# Logic_Board.net
KiCad netlist of a schematic drawn in EAGLE
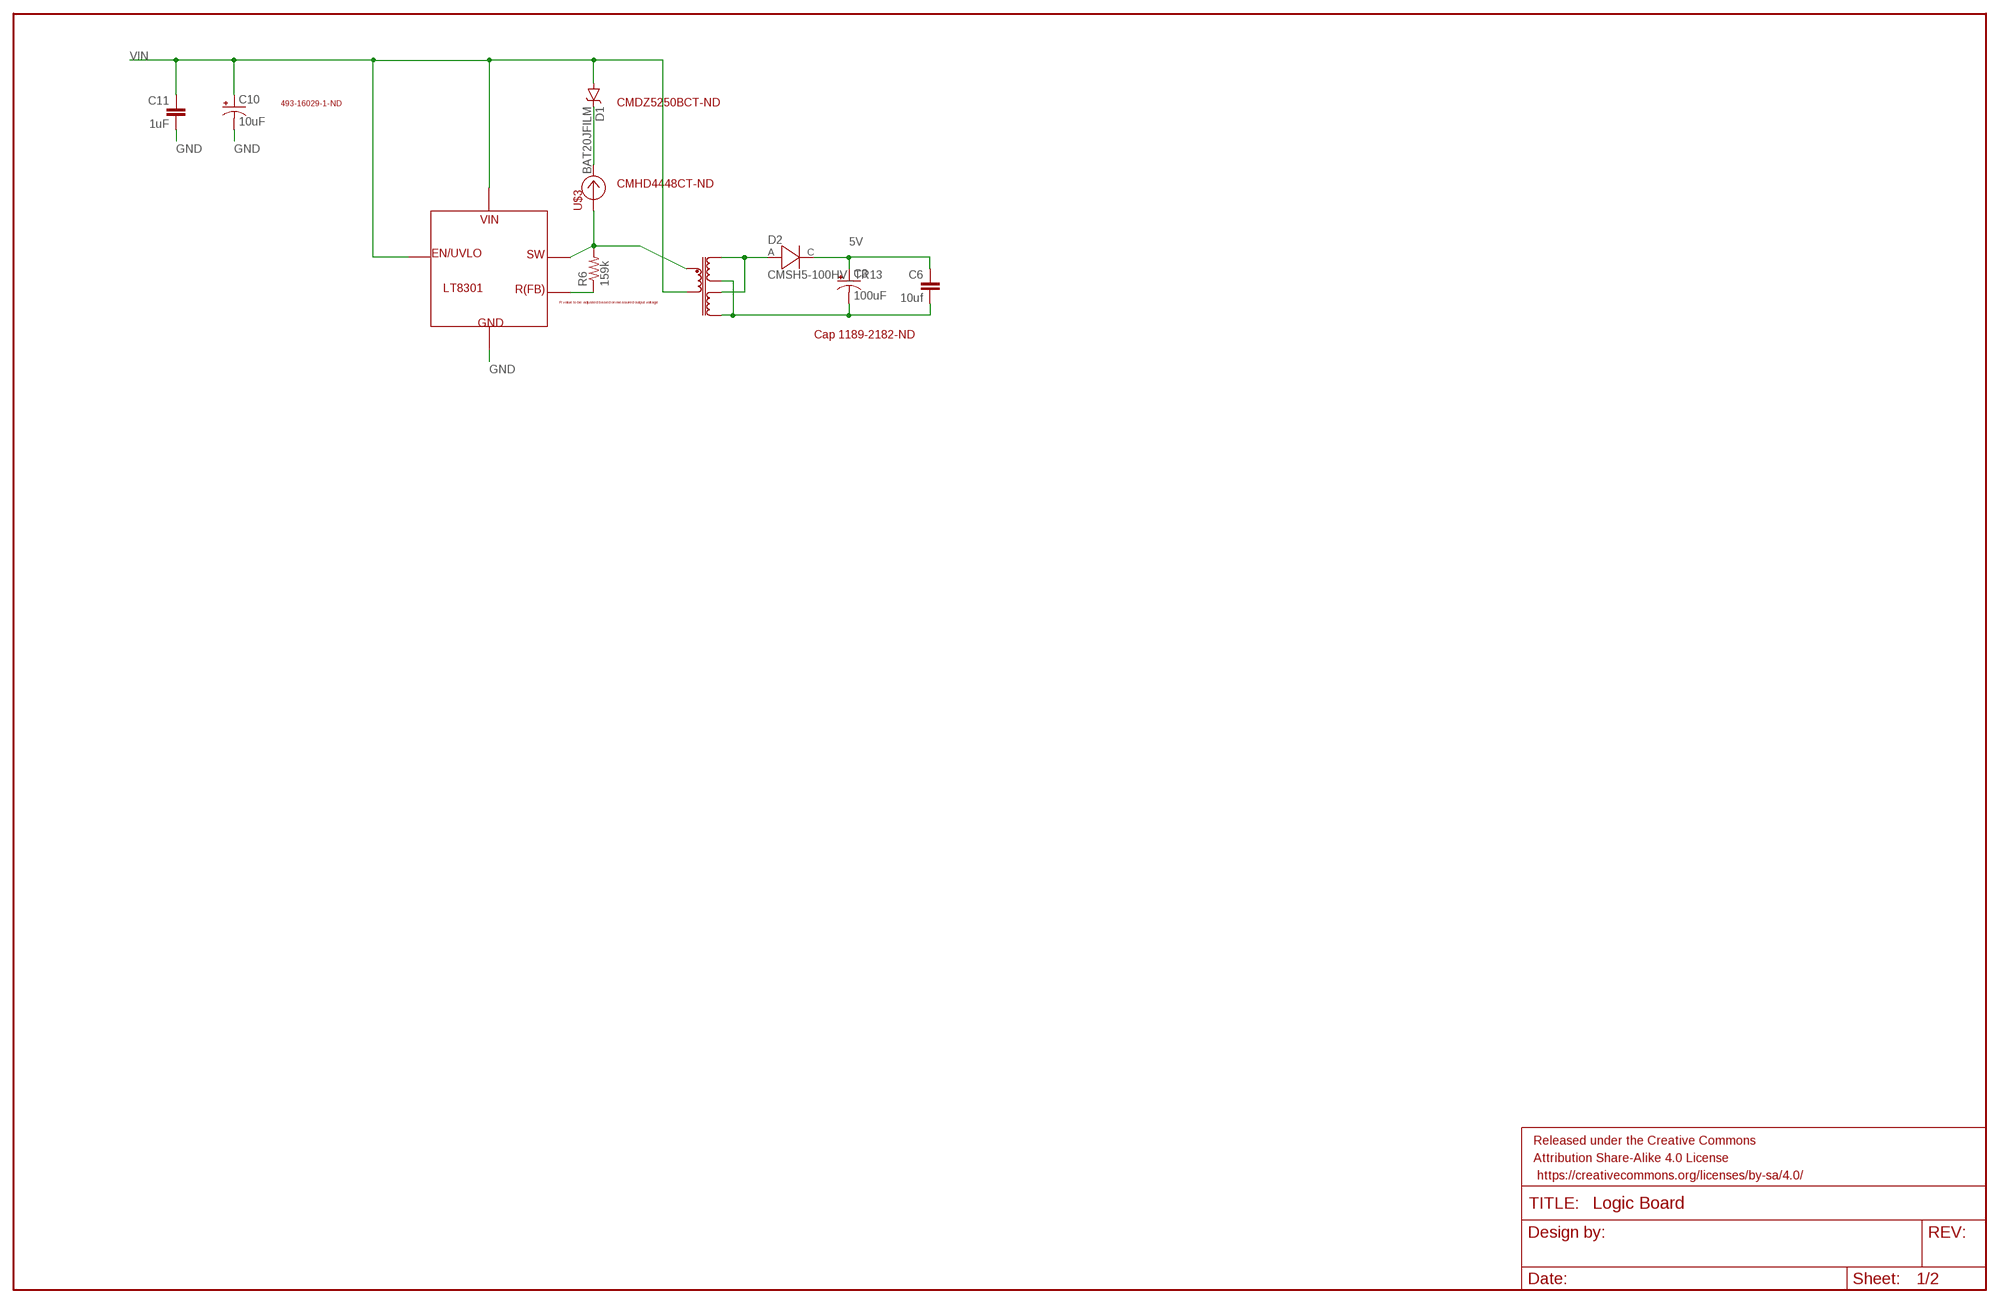
[diagram p0: schematic, sheet 1]
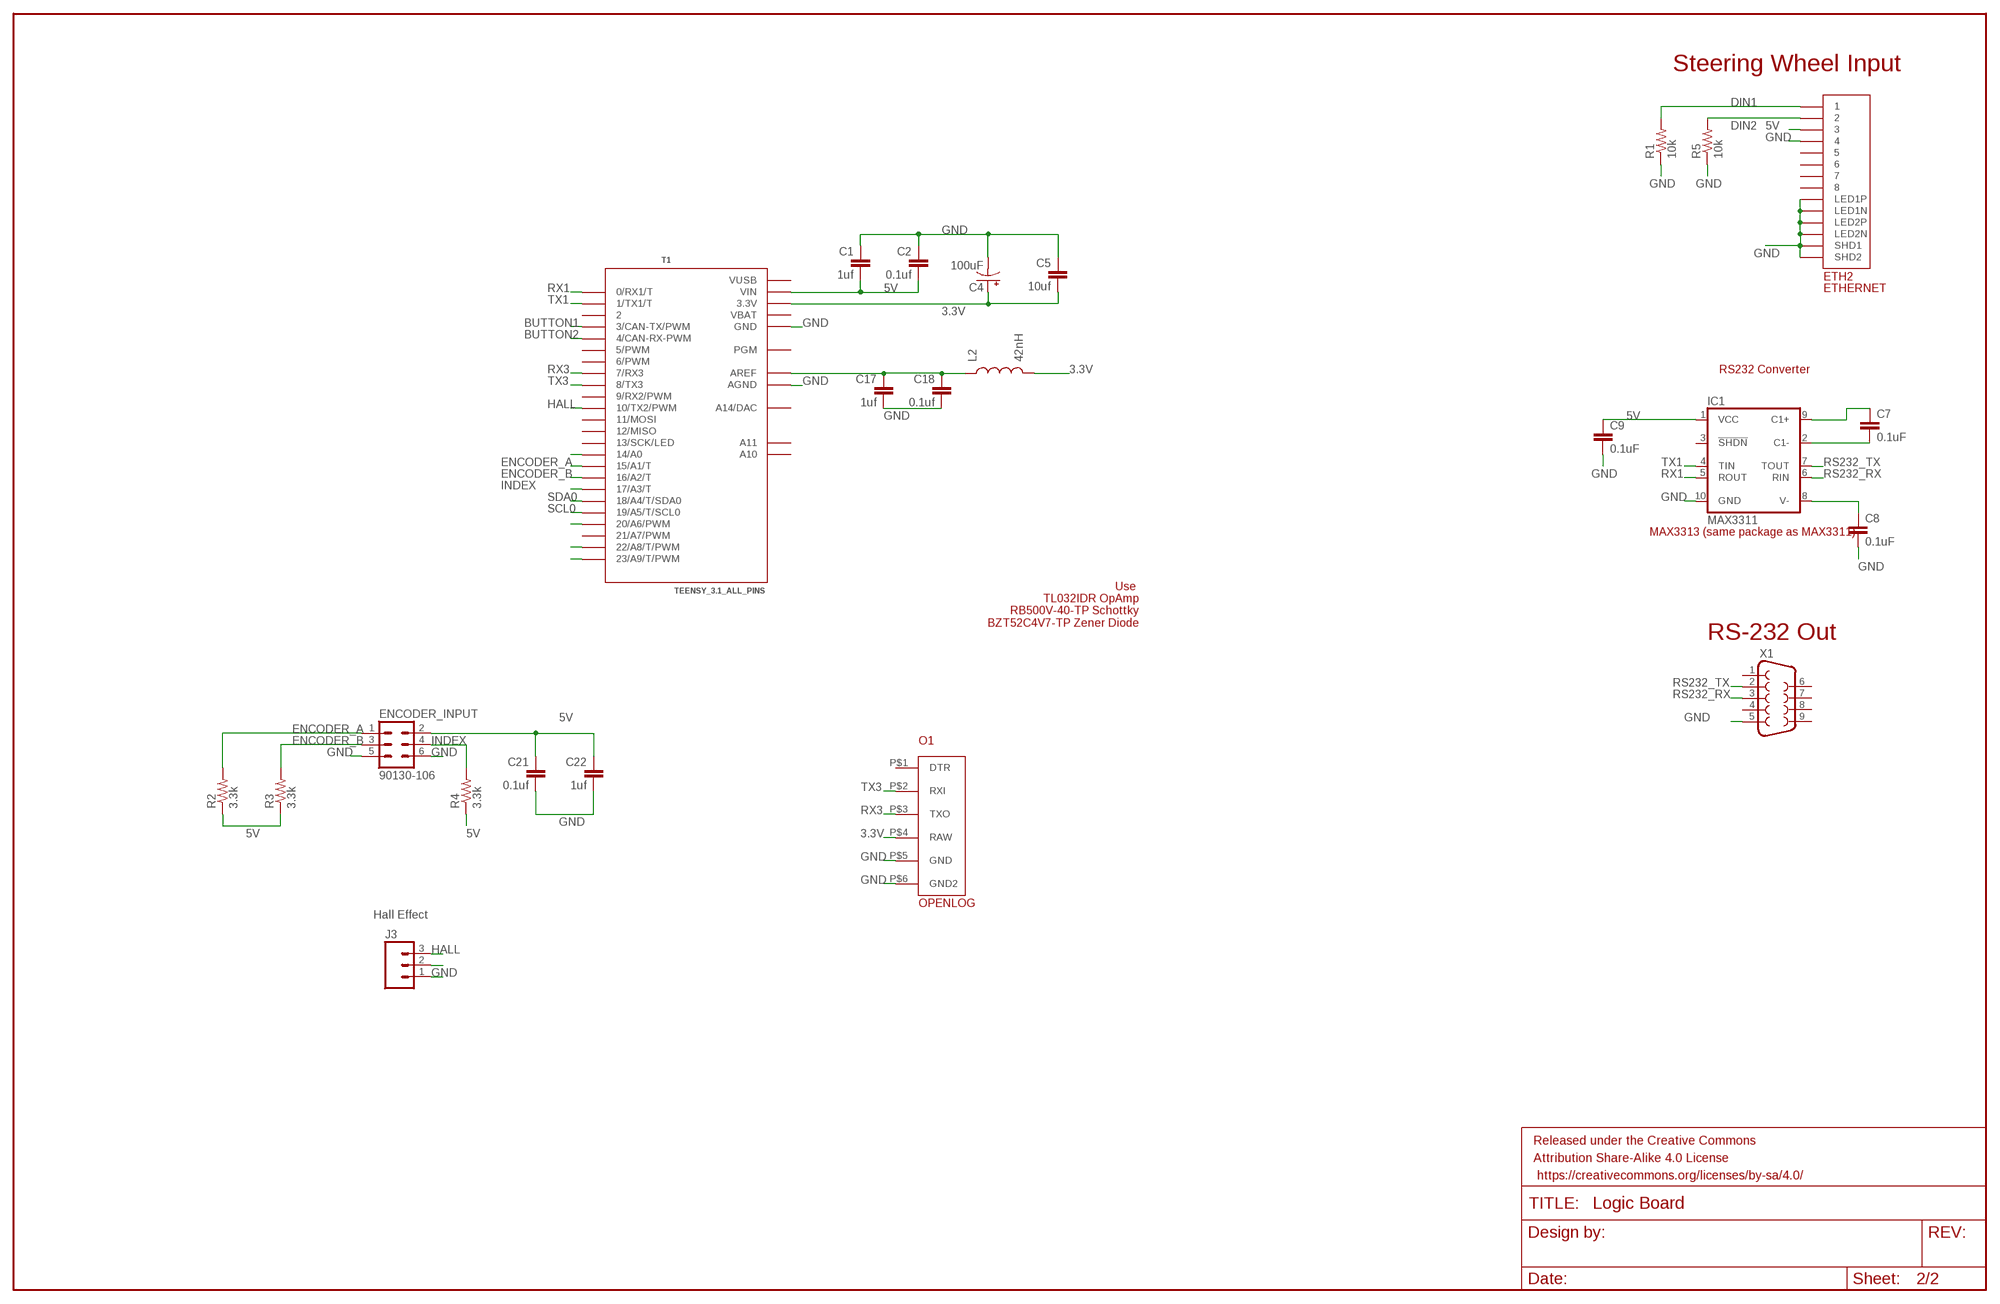
[diagram p1: schematic, sheet 2]

(export (version "E")
  (design (tool "Eeschema 10.0.6"))
  (components
    (comp (ref "C3")
      (value "100uF")
      (footprint "eagle-import:CPOL-RADIAL-2.5MM-6.5MM")
      (libsource (lib "eagle-import") (part "100UF-POLAR-RADIAL-2.5MM-25V-20%"))
    )
    (comp (ref "C6")
      (value "10uf")
      (footprint "eagle-import:C0805")
      (libsource (lib "eagle-import") (part "C-EUC0805"))
    )
    (comp (ref "C10")
      (value "10uF")
      (footprint "eagle-import:CPOL-RADIAL-100UF-25V")
      (libsource (lib "eagle-import") (part "CAP_POLPTH1"))
    )
    (comp (ref "C11")
      (value "1uF")
      (footprint "eagle-import:C0805")
      (libsource (lib "eagle-import") (part "C-EUC0805"))
    )
    (comp (ref "D1")
      (value "BAT20JFILM")
      (footprint "eagle-import:SOD-323")
      (libsource (lib "eagle-import") (part "BAT20JFILM"))
    )
    (comp (ref "D2")
      (value "CMSH5-100HV_TR13")
      (footprint "eagle-import:DIOM794X590X262L114X300N")
      (fields
        (field (name "DIGI-KEY_PART_NUMBER") "CMSH5-100HVCT-ND")
        (field (name "MF") "Central Semiconductor")
        (field (name "MP") "CMSH5-100HV TR13")
      )
      (libsource (lib "eagle-import") (part "CMSH5-100HV_TR13"))
    )
    (comp (ref "FRAME1")
      (value "FRAME-LEDGER")
      (footprint "eagle-import:CREATIVE_COMMONS")
      (libsource (lib "eagle-import") (part "FRAME-LEDGER"))
    )
    (comp (ref "R6")
      (value "159k")
      (footprint "eagle-import:R0805")
      (libsource (lib "eagle-import") (part "R-US_R0805"))
    )
    (comp (ref "U$1")
      (value "LT8301")
      (footprint "eagle-import:TSOT-23-5")
      (libsource (lib "eagle-import") (part "LT8301"))
    )
    (comp (ref "U$2")
      (value "750313974")
      (footprint "eagle-import:750313974_TRANSFORMER")
      (libsource (lib "eagle-import") (part "750313974"))
    )
    (comp (ref "U$3")
      (value "AL5809-20S1-7")
      (footprint "eagle-import:SOD-123")
      (libsource (lib "eagle-import") (part "AL5809-20S1-7"))
    )
    (comp (ref "C1")
      (value "1uf")
      (footprint "eagle-import:C0805")
      (libsource (lib "eagle-import") (part "C-EUC0805"))
    )
    (comp (ref "C2")
      (value "0.1uf")
      (footprint "eagle-import:C0805")
      (libsource (lib "eagle-import") (part "C-EUC0805"))
    )
    (comp (ref "C4")
      (value "100uF")
      (footprint "eagle-import:CPOL-RADIAL-2.5MM-6.5MM")
      (libsource (lib "eagle-import") (part "100UF-POLAR-RADIAL-2.5MM-25V-20%"))
    )
    (comp (ref "C5")
      (value "10uf")
      (footprint "eagle-import:C0805")
      (libsource (lib "eagle-import") (part "C-EUC0805"))
    )
    (comp (ref "C7")
      (value "0.1uF")
      (footprint "eagle-import:0805")
      (libsource (lib "eagle-import") (part "CAP0805"))
    )
    (comp (ref "C8")
      (value "0.1uF")
      (footprint "eagle-import:0805")
      (libsource (lib "eagle-import") (part "CAP0805"))
    )
    (comp (ref "C9")
      (value "0.1uF")
      (footprint "eagle-import:0805")
      (libsource (lib "eagle-import") (part "CAP0805"))
    )
    (comp (ref "C17")
      (value "1uf")
      (footprint "eagle-import:C0805")
      (libsource (lib "eagle-import") (part "C-EUC0805"))
    )
    (comp (ref "C18")
      (value "0.1uf")
      (footprint "eagle-import:C0805")
      (libsource (lib "eagle-import") (part "C-EUC0805"))
    )
    (comp (ref "C21")
      (value "0.1uf")
      (footprint "eagle-import:C0805")
      (libsource (lib "eagle-import") (part "C-EUC0805"))
    )
    (comp (ref "C22")
      (value "1uf")
      (footprint "eagle-import:C0805")
      (libsource (lib "eagle-import") (part "C-EUC0805"))
    )
    (comp (ref "ENCODER_INPUT")
      (value "90130-106")
      (footprint "eagle-import:90130-1_06")
      (libsource (lib "eagle-import") (part "90130-1?06"))
    )
    (comp (ref "ETH2")
      (value "ETHERNET")
      (footprint "eagle-import:A122645-ND")
      (libsource (lib "eagle-import") (part "ETHERNET"))
    )
    (comp (ref "FRAME2")
      (value "FRAME-LEDGER")
      (footprint "eagle-import:CREATIVE_COMMONS")
      (libsource (lib "eagle-import") (part "FRAME-LEDGER"))
    )
    (comp (ref "IC1")
      (value "MAX3311")
      (footprint "eagle-import:UMAX10")
      (fields (field (name "MF") "MAXIM") (field (name "MPN") "MAX3311ECUB+"))
      (libsource (lib "eagle-import") (part "MAX3311"))
    )
    (comp (ref "J3")
      (value "M03PTH")
      (footprint "eagle-import:1X03")
      (libsource (lib "eagle-import") (part "M03PTH"))
    )
    (comp (ref "L2")
      (value "42nH")
      (footprint "eagle-import:0805")
      (libsource (lib "eagle-import") (part "INDUCTOR0805"))
    )
    (comp (ref "O1")
      (value "OPENLOG")
      (footprint "eagle-import:OPENLOG")
      (libsource (lib "eagle-import") (part "OPENLOG"))
    )
    (comp (ref "R1")
      (value "10k")
      (footprint "eagle-import:0805")
      (libsource (lib "eagle-import") (part "RESISTOR0805-RES"))
    )
    (comp (ref "R2")
      (value "3.3k")
      (footprint "eagle-import:R0805")
      (libsource (lib "eagle-import") (part "R-US_R0805"))
    )
    (comp (ref "R3")
      (value "3.3k")
      (footprint "eagle-import:R0805")
      (libsource (lib "eagle-import") (part "R-US_R0805"))
    )
    (comp (ref "R4")
      (value "3.3k")
      (footprint "eagle-import:R0805")
      (libsource (lib "eagle-import") (part "R-US_R0805"))
    )
    (comp (ref "R5")
      (value "10k")
      (footprint "eagle-import:0805")
      (libsource (lib "eagle-import") (part "RESISTOR0805-RES"))
    )
    (comp (ref "T1")
      (value "TEENSY_3.1_ALL_PINS")
      (footprint "eagle-import:TEENSY3-ALL_PINS")
      (libsource (lib "eagle-import") (part "TEENSY_3.1_ALL_PINS"))
    )
    (comp (ref "X1")
      (value "F09HP")
      (footprint "eagle-import:F09HP")
      (libsource (lib "eagle-import") (part "F09HP"))
    )
  )
  (nets
    (net (code "1") (name "3.3V") (class "Default")
      (node (ref "C4") (pin "1") (pinfunction "+_1") (pintype "passive"))
      (node (ref "C5") (pin "2") (pinfunction "2_2") (pintype "passive"))
      (node (ref "L2") (pin "2") (pinfunction "2_2") (pintype "passive"))
      (node (ref "O1") (pin "P$4") (pinfunction "RAW_P$4") (pintype "bidirectional"))
      (node (ref "T1") (pin "3.3V") (pinfunction "3.3V_3.3V") (pintype "power_in"))
      (node (ref "T1") (pin "3.3V1") (pinfunction "3.3V_3.3V1") (pintype "power_in"))
    )
    (net (code "2") (name "5V") (class "Default")
      (node (ref "C1") (pin "2") (pinfunction "2_2") (pintype "passive"))
      (node (ref "C2") (pin "2") (pinfunction "2_2") (pintype "passive"))
      (node (ref "C21") (pin "1") (pinfunction "1_1") (pintype "passive"))
      (node (ref "C22") (pin "1") (pinfunction "1_1") (pintype "passive"))
      (node (ref "C3") (pin "1") (pinfunction "+_1") (pintype "passive"))
      (node (ref "C6") (pin "1") (pinfunction "1_1") (pintype "passive"))
      (node (ref "C9") (pin "1") (pinfunction "1_1") (pintype "passive"))
      (node (ref "D2") (pin "C") (pinfunction "C_C") (pintype "passive"))
      (node (ref "ENCODER_INPUT") (pin "2") (pinfunction "2_2") (pintype "passive"))
      (node (ref "ETH2") (pin "P$3") (pinfunction "3_P$3") (pintype "bidirectional"))
      (node (ref "IC1") (pin "1") (pinfunction "VCC_1") (pintype "power_in"))
      (node (ref "J3") (pin "2") (pinfunction "2_2") (pintype "passive"))
      (node (ref "R2") (pin "1") (pinfunction "1_1") (pintype "passive"))
      (node (ref "R3") (pin "1") (pinfunction "1_1") (pintype "passive"))
      (node (ref "R4") (pin "1") (pinfunction "1_1") (pintype "passive"))
      (node (ref "T1") (pin "VIN") (pinfunction "VIN_VIN") (pintype "power_in"))
    )
    (net (code "3") (name "BUTTON1") (class "Default")
      (node (ref "T1") (pin "3") (pinfunction "3/CAN-TX/PWM_3") (pintype "bidirectional"))
    )
    (net (code "4") (name "BUTTON2") (class "Default")
      (node (ref "T1") (pin "4") (pinfunction "4/CAN-RX-PWM_4") (pintype "bidirectional"))
    )
    (net (code "5") (name "DIN1") (class "Default")
      (node (ref "ETH2") (pin "P$1") (pinfunction "1_P$1") (pintype "bidirectional"))
      (node (ref "R1") (pin "2") (pinfunction "2_2") (pintype "passive"))
    )
    (net (code "6") (name "DIN2") (class "Default")
      (node (ref "ETH2") (pin "P$2") (pinfunction "2_P$2") (pintype "bidirectional"))
      (node (ref "R5") (pin "2") (pinfunction "2_2") (pintype "passive"))
    )
    (net (code "7") (name "ENCODER_A") (class "Default")
      (node (ref "ENCODER_INPUT") (pin "1") (pinfunction "1_1") (pintype "passive"))
      (node (ref "R2") (pin "2") (pinfunction "2_2") (pintype "passive"))
      (node (ref "T1") (pin "15/A1") (pinfunction "15/A1/T_15/A1") (pintype "bidirectional"))
    )
    (net (code "8") (name "ENCODER_B") (class "Default")
      (node (ref "ENCODER_INPUT") (pin "3") (pinfunction "3_3") (pintype "passive"))
      (node (ref "R3") (pin "2") (pinfunction "2_2") (pintype "passive"))
      (node (ref "T1") (pin "16/A2") (pinfunction "16/A2/T_16/A2") (pintype "bidirectional"))
    )
    (net (code "9") (name "GND") (class "Default")
      (node (ref "C1") (pin "1") (pinfunction "1_1") (pintype "passive"))
      (node (ref "C10") (pin "2") (pinfunction "-_2") (pintype "passive"))
      (node (ref "C11") (pin "2") (pinfunction "2_2") (pintype "passive"))
      (node (ref "C17") (pin "2") (pinfunction "2_2") (pintype "passive"))
      (node (ref "C18") (pin "2") (pinfunction "2_2") (pintype "passive"))
      (node (ref "C2") (pin "1") (pinfunction "1_1") (pintype "passive"))
      (node (ref "C21") (pin "2") (pinfunction "2_2") (pintype "passive"))
      (node (ref "C22") (pin "2") (pinfunction "2_2") (pintype "passive"))
      (node (ref "C4") (pin "2") (pinfunction "-_2") (pintype "passive"))
      (node (ref "C5") (pin "1") (pinfunction "1_1") (pintype "passive"))
      (node (ref "C8") (pin "2") (pinfunction "2_2") (pintype "passive"))
      (node (ref "C9") (pin "2") (pinfunction "2_2") (pintype "passive"))
      (node (ref "ENCODER_INPUT") (pin "5") (pinfunction "5_5") (pintype "passive"))
      (node (ref "ENCODER_INPUT") (pin "6") (pinfunction "6_6") (pintype "passive"))
      (node (ref "ETH2") (pin "P$10") (pinfunction "LED1P_P$10") (pintype "bidirectional"))
      (node (ref "ETH2") (pin "P$11") (pinfunction "LED2N_P$11") (pintype "bidirectional"))
      (node (ref "ETH2") (pin "P$12") (pinfunction "LED2P_P$12") (pintype "bidirectional"))
      (node (ref "ETH2") (pin "P$13") (pinfunction "SHD1_P$13") (pintype "bidirectional"))
      (node (ref "ETH2") (pin "P$14") (pinfunction "SHD2_P$14") (pintype "bidirectional"))
      (node (ref "ETH2") (pin "P$4") (pinfunction "4_P$4") (pintype "bidirectional"))
      (node (ref "ETH2") (pin "P$9") (pinfunction "LED1N_P$9") (pintype "bidirectional"))
      (node (ref "IC1") (pin "10") (pinfunction "GND_10") (pintype "power_in"))
      (node (ref "J3") (pin "1") (pinfunction "1_1") (pintype "passive"))
      (node (ref "O1") (pin "P$5") (pinfunction "GND_P$5") (pintype "bidirectional"))
      (node (ref "O1") (pin "P$6") (pinfunction "GND2_P$6") (pintype "bidirectional"))
      (node (ref "R1") (pin "1") (pinfunction "1_1") (pintype "passive"))
      (node (ref "R5") (pin "1") (pinfunction "1_1") (pintype "passive"))
      (node (ref "T1") (pin "AGND") (pinfunction "AGND_AGND") (pintype "power_in"))
      (node (ref "T1") (pin "GND") (pinfunction "GND_GND") (pintype "power_in"))
      (node (ref "T1") (pin "GND1") (pinfunction "GND_GND1") (pintype "power_in"))
      (node (ref "U$1") (pin "2.GND") (pinfunction "GND_2.GND") (pintype "bidirectional"))
      (node (ref "X1") (pin "5") (pinfunction "5_5") (pintype "passive"))
    )
    (net (code "10") (name "HALL") (class "Default")
      (node (ref "J3") (pin "3") (pinfunction "3_3") (pintype "passive"))
      (node (ref "T1") (pin "10") (pinfunction "10/TX2/PWM_10") (pintype "bidirectional"))
    )
    (net (code "11") (name "INDEX") (class "Default")
      (node (ref "ENCODER_INPUT") (pin "4") (pinfunction "4_4") (pintype "passive"))
      (node (ref "R4") (pin "2") (pinfunction "2_2") (pintype "passive"))
      (node (ref "T1") (pin "17/A3") (pinfunction "17/A3/T_17/A3") (pintype "bidirectional"))
    )
    (net (code "12") (name "Net-(C3--)") (class "Default")
      (node (ref "C3") (pin "2") (pinfunction "-_2") (pintype "passive"))
      (node (ref "C6") (pin "2") (pinfunction "2_2") (pintype "passive"))
      (node (ref "U$2") (pin "7") (pinfunction "7_7") (pintype "bidirectional"))
      (node (ref "U$2") (pin "8") (pinfunction "8_8") (pintype "bidirectional"))
    )
    (net (code "13") (name "Net-(C17-Pad1)") (class "Default")
      (node (ref "C17") (pin "1") (pinfunction "1_1") (pintype "passive"))
      (node (ref "C18") (pin "1") (pinfunction "1_1") (pintype "passive"))
      (node (ref "L2") (pin "1") (pinfunction "1_1") (pintype "passive"))
      (node (ref "T1") (pin "AREF") (pinfunction "AREF_AREF") (pintype "power_in"))
    )
    (net (code "14") (name "Net-(D1-PadC)") (class "Default")
      (node (ref "D1") (pin "C") (pinfunction "C_C") (pintype "passive"))
      (node (ref "U$3") (pin "C") (pinfunction "C_C") (pintype "bidirectional"))
    )
    (net (code "15") (name "Net-(D2-PadA)") (class "Default")
      (node (ref "D2") (pin "A") (pinfunction "A_A") (pintype "passive"))
      (node (ref "U$2") (pin "5") (pinfunction "5_5") (pintype "bidirectional"))
      (node (ref "U$2") (pin "6") (pinfunction "6_6") (pintype "bidirectional"))
    )
    (net (code "16") (name "Net-(IC1-C1+)") (class "Default")
      (node (ref "C7") (pin "1") (pinfunction "1_1") (pintype "passive"))
      (node (ref "IC1") (pin "9") (pinfunction "C1+_9") (pintype "passive"))
    )
    (net (code "17") (name "Net-(IC1-C1-)") (class "Default")
      (node (ref "C7") (pin "2") (pinfunction "2_2") (pintype "passive"))
      (node (ref "IC1") (pin "2") (pinfunction "C1-_2") (pintype "passive"))
    )
    (net (code "18") (name "Net-(IC1-V-)") (class "Default")
      (node (ref "C8") (pin "1") (pinfunction "1_1") (pintype "passive"))
      (node (ref "IC1") (pin "8") (pinfunction "V-_8") (pintype "passive"))
    )
    (net (code "19") (name "Net-(U$1-RFB)") (class "Default")
      (node (ref "R6") (pin "1") (pinfunction "1_1") (pintype "passive"))
      (node (ref "U$1") (pin "3.RFB") (pinfunction "RFB_3.RFB") (pintype "bidirectional"))
    )
    (net (code "20") (name "Net-(U$1-SW)") (class "Default")
      (node (ref "R6") (pin "2") (pinfunction "2_2") (pintype "passive"))
      (node (ref "U$1") (pin "4.SW") (pinfunction "SW_4.SW") (pintype "bidirectional"))
      (node (ref "U$2") (pin "1") (pinfunction "1_1") (pintype "bidirectional"))
      (node (ref "U$3") (pin "A") (pinfunction "A_A") (pintype "bidirectional"))
    )
    (net (code "21") (name "RS232_RX") (class "Default")
      (node (ref "IC1") (pin "6") (pinfunction "RIN_6") (pintype "input"))
      (node (ref "X1") (pin "3") (pinfunction "3_3") (pintype "passive"))
    )
    (net (code "22") (name "RS232_TX") (class "Default")
      (node (ref "IC1") (pin "7") (pinfunction "TOUT_7") (pintype "output"))
      (node (ref "X1") (pin "2") (pinfunction "2_2") (pintype "passive"))
    )
    (net (code "23") (name "RX1") (class "Default")
      (node (ref "IC1") (pin "5") (pinfunction "ROUT_5") (pintype "output"))
      (node (ref "T1") (pin "0") (pinfunction "0/RX1/T_0") (pintype "bidirectional"))
    )
    (net (code "24") (name "RX3") (class "Default")
      (node (ref "O1") (pin "P$3") (pinfunction "TXO_P$3") (pintype "bidirectional"))
      (node (ref "T1") (pin "7") (pinfunction "7/RX3_7") (pintype "bidirectional"))
    )
    (net (code "25") (name "SCL0") (class "Default")
      (node (ref "T1") (pin "19/A5") (pinfunction "19/A5/T/SCL0_19/A5") (pintype "bidirectional"))
    )
    (net (code "26") (name "SDA0") (class "Default")
      (node (ref "T1") (pin "18/A4") (pinfunction "18/A4/T/SDA0_18/A4") (pintype "bidirectional"))
    )
    (net (code "27") (name "TX1") (class "Default")
      (node (ref "IC1") (pin "4") (pinfunction "TIN_4") (pintype "input"))
      (node (ref "T1") (pin "1") (pinfunction "1/TX1/T_1") (pintype "bidirectional"))
    )
    (net (code "28") (name "TX3") (class "Default")
      (node (ref "O1") (pin "P$2") (pinfunction "RXI_P$2") (pintype "bidirectional"))
      (node (ref "T1") (pin "8") (pinfunction "8/TX3_8") (pintype "bidirectional"))
    )
    (net (code "29") (name "VBAT") (class "Default")
      (node (ref "T1") (pin "VBAT") (pinfunction "VBAT_VBAT") (pintype "power_in"))
    )
    (net (code "30") (name "VIN") (class "Default")
      (node (ref "C10") (pin "1") (pinfunction "+_1") (pintype "passive"))
      (node (ref "C11") (pin "1") (pinfunction "1_1") (pintype "passive"))
      (node (ref "D1") (pin "A") (pinfunction "A_A") (pintype "passive"))
      (node (ref "U$1") (pin "1.EN/UVLO") (pinfunction "EN/UVLO_1.EN/UVLO") (pintype "bidirectional"))
      (node (ref "U$1") (pin "5.VIN") (pinfunction "VIN_5.VIN") (pintype "bidirectional"))
      (node (ref "U$2") (pin "4") (pinfunction "4_4") (pintype "bidirectional"))
    )
    (net (code "31") (name "VUSB") (class "Default")
      (node (ref "T1") (pin "VUSB") (pinfunction "VUSB_VUSB") (pintype "power_in"))
    )
    (net (code "32") (name "unconnected-(ETH2-5-PadP$5)") (class "Default")
      (node (ref "ETH2") (pin "P$5") (pinfunction "5_P$5") (pintype "bidirectional"))
    )
    (net (code "33") (name "unconnected-(ETH2-6-PadP$6)") (class "Default")
      (node (ref "ETH2") (pin "P$6") (pinfunction "6_P$6") (pintype "bidirectional"))
    )
    (net (code "34") (name "unconnected-(ETH2-7-PadP$7)") (class "Default")
      (node (ref "ETH2") (pin "P$7") (pinfunction "7_P$7") (pintype "bidirectional"))
    )
    (net (code "35") (name "unconnected-(ETH2-8-PadP$8)") (class "Default")
      (node (ref "ETH2") (pin "P$8") (pinfunction "8_P$8") (pintype "bidirectional"))
    )
    (net (code "36") (name "unconnected-(IC1-~{SHDN}-Pad3)") (class "Default")
      (node (ref "IC1") (pin "3") (pinfunction "~{SHDN}_3") (pintype "input"))
    )
    (net (code "37") (name "unconnected-(O1-DTR-PadP$1)") (class "Default")
      (node (ref "O1") (pin "P$1") (pinfunction "DTR_P$1") (pintype "bidirectional"))
    )
    (net (code "38") (name "unconnected-(T1-5{slash}PWM-Pad5)") (class "Default")
      (node (ref "T1") (pin "5") (pinfunction "5/PWM_5") (pintype "bidirectional"))
    )
    (net (code "39") (name "unconnected-(T1-6{slash}PWM-Pad6)") (class "Default")
      (node (ref "T1") (pin "6") (pinfunction "6/PWM_6") (pintype "bidirectional"))
    )
    (net (code "40") (name "unconnected-(T1-9{slash}RX2{slash}PWM-Pad9)") (class "Default")
      (node (ref "T1") (pin "9") (pinfunction "9/RX2/PWM_9") (pintype "bidirectional"))
    )
    (net (code "41") (name "unconnected-(T1-11{slash}MOSI-Pad11)") (class "Default")
      (node (ref "T1") (pin "11") (pinfunction "11/MOSI_11") (pintype "bidirectional"))
    )
    (net (code "42") (name "unconnected-(T1-12{slash}MISO-Pad12)") (class "Default")
      (node (ref "T1") (pin "12") (pinfunction "12/MISO_12") (pintype "bidirectional"))
    )
    (net (code "43") (name "unconnected-(T1-13{slash}SCK{slash}LED-Pad13)") (class "Default")
      (node (ref "T1") (pin "13") (pinfunction "13/SCK/LED_13") (pintype "bidirectional"))
    )
    (net (code "44") (name "unconnected-(T1-20{slash}A6{slash}PWM-Pad20{slash}A6)") (class "Default")
      (node (ref "T1") (pin "20/A6") (pinfunction "20/A6/PWM_20/A6") (pintype "bidirectional"))
    )
    (net (code "45") (name "unconnected-(T1-21{slash}A7{slash}PWM-Pad21{slash}A7)") (class "Default")
      (node (ref "T1") (pin "21/A7") (pinfunction "21/A7/PWM_21/A7") (pintype "bidirectional"))
    )
    (net (code "46") (name "unconnected-(T1-22{slash}A8{slash}T{slash}PWM-Pad22{slash}A8)") (class "Default")
      (node (ref "T1") (pin "22/A8") (pinfunction "22/A8/T/PWM_22/A8") (pintype "bidirectional"))
    )
    (net (code "47") (name "unconnected-(T1-23{slash}A9{slash}T{slash}PWM-Pad23{slash}A9)") (class "Default")
      (node (ref "T1") (pin "23/A9") (pinfunction "23/A9/T/PWM_23/A9") (pintype "bidirectional"))
    )
    (net (code "48") (name "unconnected-(T1-A14{slash}DAC-PadRESET{slash}DAC)") (class "Default")
      (node (ref "T1") (pin "RESET/DAC") (pinfunction "A14/DAC_RESET/DAC") (pintype "bidirectional"))
    )
    (net (code "49") (name "unconnected-(T1-Pad2)") (class "Default")
      (node (ref "T1") (pin "2") (pinfunction "2_2") (pintype "bidirectional"))
    )
    (net (code "50") (name "unconnected-(T1-Pad14{slash}A0)") (class "Default")
      (node (ref "T1") (pin "14/A0") (pinfunction "14/A0_14/A0") (pintype "bidirectional"))
    )
    (net (code "51") (name "unconnected-(T1-PadA10)") (class "Default")
      (node (ref "T1") (pin "A10") (pinfunction "A10_A10") (pintype "bidirectional"))
    )
    (net (code "52") (name "unconnected-(T1-PadA11)") (class "Default")
      (node (ref "T1") (pin "A11") (pinfunction "A11_A11") (pintype "bidirectional"))
    )
    (net (code "53") (name "unconnected-(T1-PadPGM)") (class "Default")
      (node (ref "T1") (pin "PGM") (pinfunction "PGM_PGM") (pintype "bidirectional"))
    )
    (net (code "54") (name "unconnected-(X1-Pad1)") (class "Default")
      (node (ref "X1") (pin "1") (pinfunction "1_1") (pintype "passive"))
    )
    (net (code "55") (name "unconnected-(X1-Pad4)") (class "Default")
      (node (ref "X1") (pin "4") (pinfunction "4_4") (pintype "passive"))
    )
    (net (code "56") (name "unconnected-(X1-Pad6)") (class "Default")
      (node (ref "X1") (pin "6") (pinfunction "6_6") (pintype "passive"))
    )
    (net (code "57") (name "unconnected-(X1-Pad7)") (class "Default")
      (node (ref "X1") (pin "7") (pinfunction "7_7") (pintype "passive"))
    )
    (net (code "58") (name "unconnected-(X1-Pad8)") (class "Default")
      (node (ref "X1") (pin "8") (pinfunction "8_8") (pintype "passive"))
    )
    (net (code "59") (name "unconnected-(X1-Pad9)") (class "Default")
      (node (ref "X1") (pin "9") (pinfunction "9_9") (pintype "passive"))
    )
  )
)
